# USB.net
KiCad netlist of a schematic drawn in Altium Designer
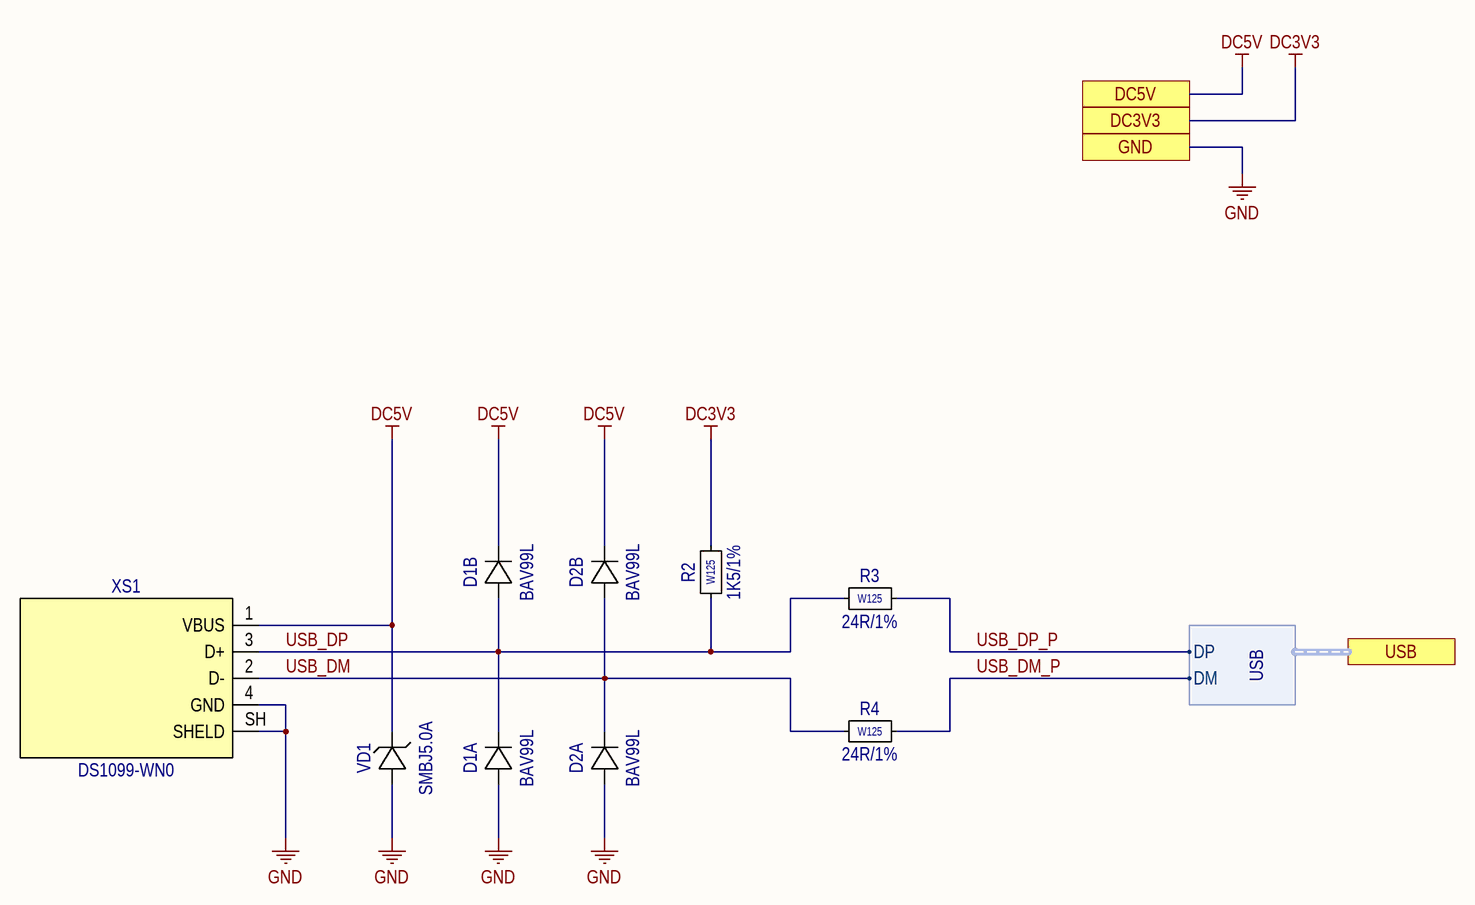
[diagram p0: USB.SchDoc]

(export (version "E")
  (design (tool "Eeschema 10.0.6"))
  (components
    (comp (ref "D1")
      (value "BAV99L")
      (footprint "3-SOT23")
      (libsource (lib "mfmc_components") (part "BAV99L"))
    )
    (comp (ref "D2")
      (value "BAV99L")
      (footprint "3-SOT23")
      (libsource (lib "mfmc_components") (part "BAV99L"))
    )
    (comp (ref "R2")
      (value "1K5/1%")
      (footprint "SMD_RES_0805-L2000-W1250-H500-M1501")
      (description "Film resistor SMD 0805")
      (fields (field (name "Comment") "CR0805-1K5-1%"))
      (libsource (lib "ChipResistors-0805-E24") (part "CR0805-1K5-1%"))
    )
    (comp (ref "R3")
      (value "24R/1%")
      (footprint "SMD_RES_0805-L2000-W1250-H500-M24R0")
      (description "Film resistor SMD 0805")
      (fields (field (name "Comment") "CR0805-24R-1%"))
      (libsource (lib "ChipResistors-0805-E24") (part "CR0805-24R-1%"))
    )
    (comp (ref "R4")
      (value "24R/1%")
      (footprint "SMD_RES_0805-L2000-W1250-H500-M24R0")
      (description "Film resistor SMD 0805")
      (fields (field (name "Comment") "CR0805-24R-1%"))
      (libsource (lib "ChipResistors-0805-E24") (part "CR0805-24R-1%"))
    )
    (comp (ref "VD1")
      (value "SMBJ5.0A")
      (footprint "2-MOLDED-E4600-D4000-A2700-H5600-B2200")
      (libsource (lib "mfmc_components") (part "SMBJ5.0A"))
    )
    (comp (ref "XS1")
      (value "DS1099-WN0")
      (footprint "DS1099")
      (description "USB Type-B R/A DIP Type Connector")
      (fields (field (name "MANUFACTURER") "Connfly Electronic Co. Ltd"))
      (libsource (lib "mfmc_components") (part "DS1099-WN0"))
    )
  )
  (nets
    (net (code "2") (name "/USB_DM") (class "Default")
      (node (ref "D2") (pin "3") (pinfunction "3_3") (pintype "passive"))
      (node (ref "R4") (pin "1") (pintype "passive"))
      (node (ref "XS1") (pin "2") (pinfunction "D-_2") (pintype "passive"))
    )
    (net (code "3") (name "/USB_DM_P") (class "Default") (node (ref "R4") (pin "2") (pintype "passive")))
    (net (code "4") (name "/USB_DP") (class "Default")
      (node (ref "D1") (pin "3") (pinfunction "3_3") (pintype "passive"))
      (node (ref "R2") (pin "1") (pintype "passive"))
      (node (ref "R3") (pin "1") (pintype "passive"))
      (node (ref "XS1") (pin "3") (pinfunction "D+_3") (pintype "passive"))
    )
    (net (code "5") (name "/USB_DP_P") (class "Default") (node (ref "R3") (pin "2") (pintype "passive")))
    (net (code "7") (name "DC3V3") (class "Default") (node (ref "R2") (pin "2") (pintype "passive")))
    (net (code "8") (name "DC5V") (class "Default")
      (node (ref "D1") (pin "2") (pinfunction "2_2") (pintype "passive"))
      (node (ref "D2") (pin "2") (pinfunction "2_2") (pintype "passive"))
      (node (ref "VD1") (pin "1") (pinfunction "1_1") (pintype "passive"))
      (node (ref "XS1") (pin "1") (pinfunction "VBUS_1") (pintype "passive"))
    )
    (net (code "9") (name "GND") (class "Default")
      (node (ref "D1") (pin "1") (pinfunction "1_1") (pintype "passive"))
      (node (ref "D2") (pin "1") (pinfunction "1_1") (pintype "passive"))
      (node (ref "VD1") (pin "2") (pinfunction "2_2") (pintype "passive"))
      (node (ref "XS1") (pin "4") (pinfunction "GND_4") (pintype "passive"))
      (node (ref "XS1") (pin "SH") (pinfunction "SHELD_SH") (pintype "passive"))
    )
  )
)
